# ACS712-v12.net
KiCad netlist of a schematic drawn in EAGLE
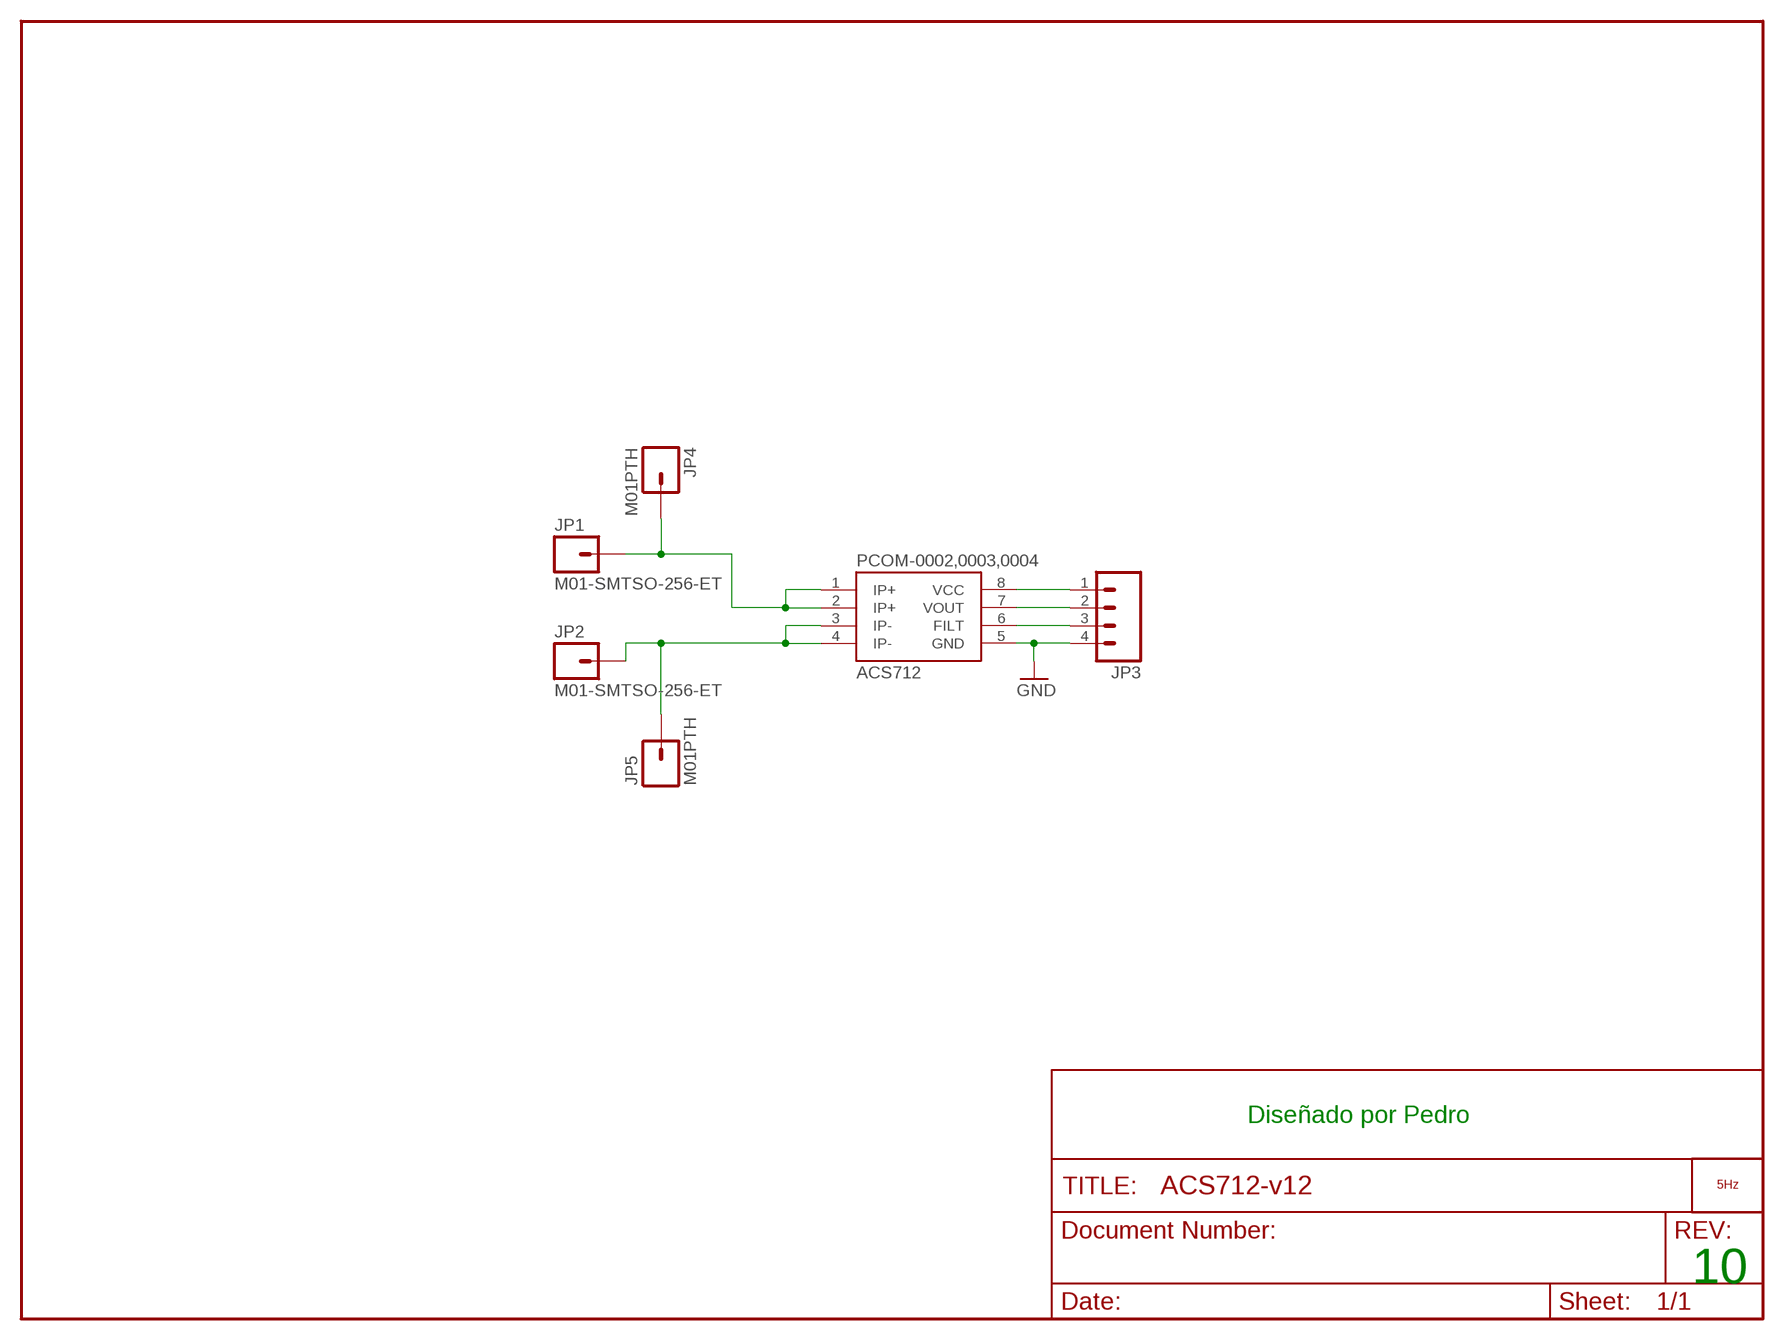
[diagram p0: schematic, sheet 1]

(export (version "E")
  (design (tool "Eeschema 10.0.6"))
  (components
    (comp (ref "JP1")
      (value "M01-SMTSO-256-ET")
      (footprint "eagle-import:SMTSO-256-ET")
      (libsource (lib "eagle-import") (part "M01-SMTSO-256-ET"))
    )
    (comp (ref "JP2")
      (value "M01-SMTSO-256-ET")
      (footprint "eagle-import:SMTSO-256-ET")
      (libsource (lib "eagle-import") (part "M01-SMTSO-256-ET"))
    )
    (comp (ref "JP3")
      (value "M04PTH")
      (footprint "eagle-import:1X04")
      (libsource (lib "eagle-import") (part "M04PTH"))
    )
    (comp (ref "JP4")
      (value "M01PTH")
      (footprint "eagle-import:1X01")
      (libsource (lib "eagle-import") (part "M01PTH"))
    )
    (comp (ref "JP5")
      (value "M01PTH")
      (footprint "eagle-import:1X01")
      (libsource (lib "eagle-import") (part "M01PTH"))
    )
    (comp (ref "LOGO1")
      (value "LOGO_5HZ_H_10MM")
      (footprint "eagle-import:5HZ_LOGO_H_10MM")
      (libsource (lib "eagle-import") (part "LOGO_5HZ_H_10MM"))
    )
    (comp (ref "PCOM-0002,0003,0004")
      (value "ACS712")
      (footprint "eagle-import:SO08")
      (libsource (lib "eagle-import") (part "ACS712"))
    )
  )
  (nets
    (net (code "1") (name "GND") (class "Default")
      (node (ref "JP3") (pin "4") (pinfunction "4_4") (pintype "passive"))
      (node (ref "PCOM-0002,0003,0004") (pin "5") (pinfunction "GND_5") (pintype "bidirectional"))
    )
    (net (code "2") (name "Net-(JP1-1)") (class "Default")
      (node (ref "JP1") (pin "P$1") (pinfunction "1_P$1") (pintype "passive"))
      (node (ref "JP4") (pin "1") (pinfunction "1_1") (pintype "passive"))
      (node (ref "PCOM-0002,0003,0004") (pin "1") (pinfunction "IP+_1") (pintype "bidirectional"))
      (node (ref "PCOM-0002,0003,0004") (pin "2") (pinfunction "IP+_2") (pintype "bidirectional"))
    )
    (net (code "3") (name "Net-(JP2-1)") (class "Default")
      (node (ref "JP2") (pin "P$1") (pinfunction "1_P$1") (pintype "passive"))
      (node (ref "JP5") (pin "1") (pinfunction "1_1") (pintype "passive"))
      (node (ref "PCOM-0002,0003,0004") (pin "3") (pinfunction "IP-_3") (pintype "bidirectional"))
      (node (ref "PCOM-0002,0003,0004") (pin "4") (pinfunction "IP-_4") (pintype "bidirectional"))
    )
    (net (code "4") (name "Net-(PCOM-0002,0003,0004-FILT)") (class "Default")
      (node (ref "JP3") (pin "3") (pinfunction "3_3") (pintype "passive"))
      (node (ref "PCOM-0002,0003,0004") (pin "6") (pinfunction "FILT_6") (pintype "bidirectional"))
    )
    (net (code "5") (name "Net-(PCOM-0002,0003,0004-VCC)") (class "Default")
      (node (ref "JP3") (pin "1") (pinfunction "1_1") (pintype "passive"))
      (node (ref "PCOM-0002,0003,0004") (pin "8") (pinfunction "VCC_8") (pintype "bidirectional"))
    )
    (net (code "6") (name "Net-(PCOM-0002,0003,0004-VOUT)") (class "Default")
      (node (ref "JP3") (pin "2") (pinfunction "2_2") (pintype "passive"))
      (node (ref "PCOM-0002,0003,0004") (pin "7") (pinfunction "VOUT_7") (pintype "bidirectional"))
    )
  )
)
